# Pump_Driver_Test.net
KiCad netlist of a schematic drawn in Altium Designer
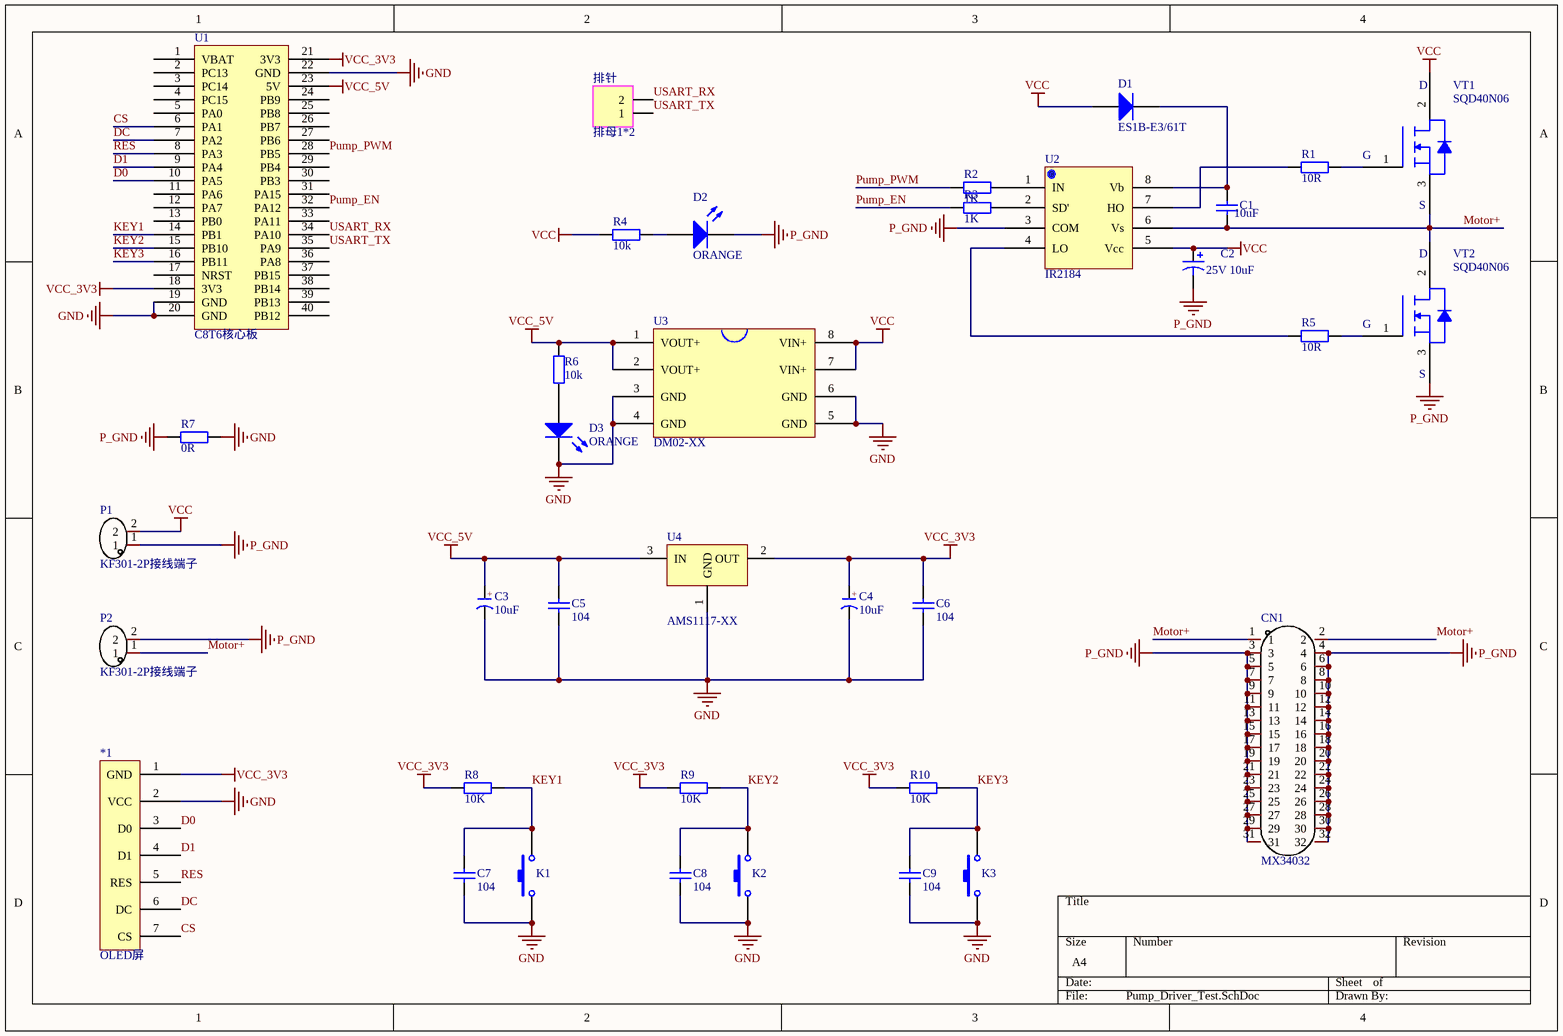
[diagram p0: Pump_Driver_Test.SchDoc]

(export (version "E")
  (design (tool "Eeschema 10.0.6"))
  (components
    (comp (ref "*1") (value "OLED屏") (footprint "HDR2.54-M-LI-7P") (libsource (lib "手柄按钮") (part "OLED屏")))
    (comp (ref "C1")
      (value "10uF")
      (footprint "C 0805")
      (description "无极性电容")
      (libsource (lib "ER100_ESC") (part "Cap"))
    )
    (comp (ref "C2")
      (value "25V 10uF")
      (footprint "CP 3528B")
      (description "极性电容")
      (libsource (lib "ER100_ESC") (part "Cap_Pol"))
    )
    (comp (ref "C3")
      (value "10uF")
      (footprint "CD B(3528)")
      (libsource (lib "USB_Gamepad_board") (part "贴片钽电容"))
    )
    (comp (ref "C4")
      (value "10uF")
      (footprint "CD B(3528)")
      (libsource (lib "USB_Gamepad_board") (part "贴片钽电容"))
    )
    (comp (ref "C5")
      (value "104")
      (footprint "C 0805")
      (description "无极性电容")
      (libsource (lib "HRT_D Schlib") (part "Cap"))
    )
    (comp (ref "C6")
      (value "104")
      (footprint "C 0805")
      (description "无极性电容")
      (libsource (lib "HRT_D Schlib") (part "Cap"))
    )
    (comp (ref "C7")
      (value "104")
      (footprint "C 0805")
      (description "无极性电容")
      (libsource (lib "HRT_D Schlib") (part "Cap"))
    )
    (comp (ref "C8")
      (value "104")
      (footprint "C 0805")
      (description "无极性电容")
      (libsource (lib "HRT_D Schlib") (part "Cap"))
    )
    (comp (ref "C9")
      (value "104")
      (footprint "C 0805")
      (description "无极性电容")
      (libsource (lib "HRT_D Schlib") (part "Cap"))
    )
    (comp (ref "CN1")
      (value "MX34032NF2")
      (footprint "CONN-TH_MX34032NF2")
      (description "间距:2.2mm;插针结构:2x16P;排数:2;每排PIN数:16;行距:3mm;公母:公型插针;安装方式:弯插;")
      (fields (field (name "MANUFACTURER") "JAE(日本航空电子)") (field (name "NAME") "MX34032"))
      (libsource (lib "MX34032") (part "MX34032NF2"))
    )
    (comp (ref "D1")
      (value "ES1B-E3/61T")
      (footprint "DO-214")
      (description "二极管")
      (libsource (lib "ER100_ESC") (part "Diode"))
    )
    (comp (ref "D2")
      (value "ORANGE")
      (footprint "LED_0805")
      (description "发光二极管")
      (libsource (lib "ESC_control") (part "LED"))
    )
    (comp (ref "D3")
      (value "ORANGE")
      (footprint "LED_0805")
      (description "发光二极管")
      (libsource (lib "ESC_control") (part "LED"))
    )
    (comp (ref "K1")
      (value "Key")
      (footprint "KEY 3.6*2.5 SMD")
      (description "按键")
      (libsource (lib "HRT_D Schlib") (part "Key"))
    )
    (comp (ref "K2")
      (value "Key")
      (footprint "KEY 3.6*2.5 SMD")
      (description "按键")
      (libsource (lib "HRT_D Schlib") (part "Key"))
    )
    (comp (ref "K3")
      (value "Key")
      (footprint "KEY 3.6*2.5 SMD")
      (description "按键")
      (libsource (lib "HRT_D Schlib") (part "Key"))
    )
    (comp (ref "P1")
      (value "KF301-2P接线端子")
      (footprint "CONN-TH_XY301V-A-5.0-2P")
      (fields (field (name "NAME") "KF301-2P接线端子"))
      (libsource (lib "KF301_2P") (part "KF301-2P接线端子"))
    )
    (comp (ref "P2")
      (value "KF301-2P接线端子")
      (footprint "CONN-TH_XY301V-A-5.0-2P")
      (fields (field (name "NAME") "KF301-2P接线端子"))
      (libsource (lib "KF301_2P") (part "KF301-2P接线端子"))
    )
    (comp (ref "R1")
      (value "10R")
      (footprint "R 0805")
      (description "电阻")
      (libsource (lib "ER100_ESC") (part "Resistor"))
    )
    (comp (ref "R2")
      (value "1K")
      (footprint "R 0805")
      (description "电阻")
      (libsource (lib "ER100_ESC") (part "Resistor"))
    )
    (comp (ref "R3")
      (value "1K")
      (footprint "R 0805")
      (description "电阻")
      (libsource (lib "ER100_ESC") (part "Resistor"))
    )
    (comp (ref "R4")
      (value "10k")
      (footprint "R 0805")
      (description "电阻")
      (libsource (lib "ESC_control") (part "Resistor"))
    )
    (comp (ref "R5")
      (value "10R")
      (footprint "R 0805")
      (description "电阻")
      (libsource (lib "ER100_ESC") (part "Resistor"))
    )
    (comp (ref "R6")
      (value "10k")
      (footprint "R 0805")
      (description "电阻")
      (libsource (lib "") (part "Resistor_1"))
    )
    (comp (ref "R7")
      (value "0R")
      (footprint "R 0805")
      (description "电阻")
      (libsource (lib "HRT_D Schlib") (part "Resistor"))
    )
    (comp (ref "R8")
      (value "10K")
      (footprint "R 0805")
      (description "电阻")
      (libsource (lib "ESC_control") (part "Resistor"))
    )
    (comp (ref "R9")
      (value "10K")
      (footprint "R 0805")
      (description "电阻")
      (libsource (lib "ESC_control") (part "Resistor"))
    )
    (comp (ref "R10")
      (value "10K")
      (footprint "R 0805")
      (description "电阻")
      (libsource (lib "ESC_control") (part "Resistor"))
    )
    (comp (ref "U1")
      (value "C8T6核心板")
      (footprint "c8t6核心板")
      (libsource (lib "STM32F103C8T6最小系统板") (part "C8T6核心板"))
    )
    (comp (ref "U2")
      (value "IR2184")
      (footprint "SOP8")
      (description "Half-Bridge Gate Driver")
      (libsource (lib "ER100_ESC") (part "IR2184"))
    )
    (comp (ref "U3")
      (value "DM02-XX")
      (footprint "DM02")
      (description "开关型DC-DC变换器")
      (libsource (lib "ESC_control") (part "DM02"))
    )
    (comp (ref "U4")
      (value "AMS1117-XX")
      (footprint "SOT223")
      (description "线性稳压器")
      (libsource (lib "HRT_D Schlib") (part "AMS1117"))
    )
    (comp (ref "VT1")
      (value "SQD40N06")
      (footprint "TO263-3B")
      (libsource (lib "ER100_ESC") (part "PowerMos_N"))
    )
    (comp (ref "VT2")
      (value "SQD40N06")
      (footprint "TO263-3B")
      (libsource (lib "ER100_ESC") (part "PowerMos_N"))
    )
    (comp (ref "排针") (value "排母1*2") (footprint "HDR2.54-M-LI-2P") (libsource (lib "排针排母库") (part "排母1*2")))
  )
  (nets
    (net (code "1") (name "/CS") (class "Default")
      (node (ref "*1") (pin "7") (pinfunction "CS_7") (pintype "passive"))
      (node (ref "U1") (pin "6") (pinfunction "PA1_6") (pintype "passive"))
    )
    (net (code "2") (name "/D0") (class "Default")
      (node (ref "*1") (pin "3") (pinfunction "D0_3") (pintype "passive"))
      (node (ref "U1") (pin "10") (pinfunction "PA5_10") (pintype "passive"))
    )
    (net (code "3") (name "/D1") (class "Default")
      (node (ref "*1") (pin "4") (pinfunction "D1_4") (pintype "passive"))
      (node (ref "U1") (pin "9") (pinfunction "PA4_9") (pintype "passive"))
    )
    (net (code "4") (name "/DC") (class "Default")
      (node (ref "*1") (pin "6") (pinfunction "DC_6") (pintype "passive"))
      (node (ref "U1") (pin "7") (pinfunction "PA2_7") (pintype "passive"))
    )
    (net (code "5") (name "/KEY1") (class "Default")
      (node (ref "C7") (pin "1") (pinfunction "1_1") (pintype "passive"))
      (node (ref "K1") (pin "2") (pinfunction "2_2") (pintype "passive"))
      (node (ref "R8") (pin "1") (pinfunction "1_1") (pintype "passive"))
      (node (ref "U1") (pin "14") (pinfunction "PB1_14") (pintype "passive"))
    )
    (net (code "6") (name "/KEY2") (class "Default")
      (node (ref "C8") (pin "1") (pinfunction "1_1") (pintype "passive"))
      (node (ref "K2") (pin "2") (pinfunction "2_2") (pintype "passive"))
      (node (ref "R9") (pin "1") (pinfunction "1_1") (pintype "passive"))
      (node (ref "U1") (pin "15") (pinfunction "PB10_15") (pintype "passive"))
    )
    (net (code "7") (name "/KEY3") (class "Default")
      (node (ref "C9") (pin "1") (pinfunction "1_1") (pintype "passive"))
      (node (ref "K3") (pin "2") (pinfunction "2_2") (pintype "passive"))
      (node (ref "R10") (pin "1") (pinfunction "1_1") (pintype "passive"))
      (node (ref "U1") (pin "16") (pinfunction "PB11_16") (pintype "passive"))
    )
    (net (code "8") (name "/Motor+") (class "Default")
      (node (ref "C1") (pin "1") (pinfunction "1_1") (pintype "passive"))
      (node (ref "CN1") (pin "1") (pinfunction "1_1") (pintype "passive"))
      (node (ref "CN1") (pin "2") (pinfunction "2_2") (pintype "passive"))
      (node (ref "P2") (pin "1") (pinfunction "1_1") (pintype "passive"))
      (node (ref "U2") (pin "6") (pinfunction "Vs_6") (pintype "passive"))
      (node (ref "VT1") (pin "3") (pinfunction "3_3") (pintype "passive"))
      (node (ref "VT2") (pin "2") (pinfunction "2_2") (pintype "passive"))
    )
    (net (code "9") (name "/Pump_EN") (class "Default")
      (node (ref "R3") (pin "1") (pinfunction "1_1") (pintype "passive"))
      (node (ref "U1") (pin "32") (pinfunction "PA12_32") (pintype "passive"))
    )
    (net (code "10") (name "/Pump_PWM") (class "Default")
      (node (ref "R2") (pin "1") (pinfunction "1_1") (pintype "passive"))
      (node (ref "U1") (pin "28") (pinfunction "PB5_28") (pintype "passive"))
    )
    (net (code "11") (name "/RES") (class "Default")
      (node (ref "*1") (pin "5") (pinfunction "RES_5") (pintype "passive"))
      (node (ref "U1") (pin "8") (pinfunction "PA3_8") (pintype "passive"))
    )
    (net (code "12") (name "/USART_RX") (class "Default")
      (node (ref "U1") (pin "34") (pinfunction "PA10_34") (pintype "passive"))
      (node (ref "排针") (pin "2") (pinfunction "2_2") (pintype "passive"))
    )
    (net (code "13") (name "/USART_TX") (class "Default")
      (node (ref "U1") (pin "35") (pinfunction "PA9_35") (pintype "passive"))
      (node (ref "排针") (pin "1") (pinfunction "1_1") (pintype "passive"))
    )
    (net (code "14") (name "GND") (class "Default")
      (node (ref "*1") (pin "2") (pinfunction "VCC_2") (pintype "passive"))
      (node (ref "C3") (pin "2") (pinfunction "K_2") (pintype "passive"))
      (node (ref "C4") (pin "2") (pinfunction "K_2") (pintype "passive"))
      (node (ref "C5") (pin "2") (pinfunction "2_2") (pintype "passive"))
      (node (ref "C6") (pin "2") (pinfunction "2_2") (pintype "passive"))
      (node (ref "C7") (pin "2") (pinfunction "2_2") (pintype "passive"))
      (node (ref "C8") (pin "2") (pinfunction "2_2") (pintype "passive"))
      (node (ref "C9") (pin "2") (pinfunction "2_2") (pintype "passive"))
      (node (ref "D3") (pin "2") (pinfunction "K_2") (pintype "passive"))
      (node (ref "K1") (pin "1") (pinfunction "1_1") (pintype "passive"))
      (node (ref "K2") (pin "1") (pinfunction "1_1") (pintype "passive"))
      (node (ref "K3") (pin "1") (pinfunction "1_1") (pintype "passive"))
      (node (ref "R7") (pin "2") (pinfunction "2_2") (pintype "passive"))
      (node (ref "U1") (pin "19") (pinfunction "GND_19") (pintype "passive"))
      (node (ref "U1") (pin "20") (pinfunction "GND_20") (pintype "passive"))
      (node (ref "U1") (pin "22") (pinfunction "GND_22") (pintype "passive"))
      (node (ref "U3") (pin "3") (pinfunction "GND_3") (pintype "passive"))
      (node (ref "U3") (pin "4") (pinfunction "GND_4") (pintype "passive"))
      (node (ref "U3") (pin "5") (pinfunction "GND_5") (pintype "passive"))
      (node (ref "U3") (pin "6") (pinfunction "GND_6") (pintype "passive"))
      (node (ref "U4") (pin "1") (pinfunction "GND_1") (pintype "power_in"))
    )
    (net (code "15") (name "Net-(D1-K)") (class "Default")
      (node (ref "C1") (pin "2") (pinfunction "2_2") (pintype "passive"))
      (node (ref "D1") (pin "2") (pinfunction "K_2") (pintype "passive"))
      (node (ref "U2") (pin "8") (pinfunction "Vb_8") (pintype "passive"))
    )
    (net (code "16") (name "Net-(D2-A)") (class "Default")
      (node (ref "D2") (pin "1") (pinfunction "A_1") (pintype "passive"))
      (node (ref "R4") (pin "1") (pinfunction "1_1") (pintype "passive"))
    )
    (net (code "17") (name "Net-(D3-A)") (class "Default")
      (node (ref "D3") (pin "1") (pinfunction "A_1") (pintype "passive"))
      (node (ref "R6") (pin "1") (pinfunction "1_1") (pintype "passive"))
    )
    (net (code "18") (name "Net-(U2-HO)") (class "Default")
      (node (ref "R1") (pin "1") (pinfunction "1_1") (pintype "passive"))
      (node (ref "U2") (pin "7") (pinfunction "HO_7") (pintype "passive"))
    )
    (net (code "19") (name "Net-(U2-IN)") (class "Default")
      (node (ref "R2") (pin "2") (pinfunction "2_2") (pintype "passive"))
      (node (ref "U2") (pin "1") (pinfunction "IN_1") (pintype "passive"))
    )
    (net (code "20") (name "Net-(U2-LO)") (class "Default")
      (node (ref "R5") (pin "1") (pinfunction "1_1") (pintype "passive"))
      (node (ref "U2") (pin "4") (pinfunction "LO_4") (pintype "passive"))
    )
    (net (code "21") (name "Net-(U2-SD')") (class "Default")
      (node (ref "R3") (pin "2") (pinfunction "2_2") (pintype "passive"))
      (node (ref "U2") (pin "2") (pinfunction "SD'_2") (pintype "passive"))
    )
    (net (code "22") (name "Net-(VT1-G)") (class "Default")
      (node (ref "R1") (pin "2") (pinfunction "2_2") (pintype "passive"))
      (node (ref "VT1") (pin "1") (pinfunction "G_1") (pintype "passive"))
    )
    (net (code "23") (name "Net-(VT2-G)") (class "Default")
      (node (ref "R5") (pin "2") (pinfunction "2_2") (pintype "passive"))
      (node (ref "VT2") (pin "1") (pinfunction "G_1") (pintype "passive"))
    )
    (net (code "24") (name "P_GND") (class "Default")
      (node (ref "C2") (pin "2") (pinfunction "2_2") (pintype "passive"))
      (node (ref "CN1") (pin "10") (pinfunction "10_10") (pintype "passive"))
      (node (ref "CN1") (pin "11") (pinfunction "11_11") (pintype "passive"))
      (node (ref "CN1") (pin "12") (pinfunction "12_12") (pintype "passive"))
      (node (ref "CN1") (pin "13") (pinfunction "13_13") (pintype "passive"))
      (node (ref "CN1") (pin "14") (pinfunction "14_14") (pintype "passive"))
      (node (ref "CN1") (pin "15") (pinfunction "15_15") (pintype "passive"))
      (node (ref "CN1") (pin "16") (pinfunction "16_16") (pintype "passive"))
      (node (ref "CN1") (pin "17") (pinfunction "17_17") (pintype "passive"))
      (node (ref "CN1") (pin "18") (pinfunction "18_18") (pintype "passive"))
      (node (ref "CN1") (pin "19") (pinfunction "19_19") (pintype "passive"))
      (node (ref "CN1") (pin "20") (pinfunction "20_20") (pintype "passive"))
      (node (ref "CN1") (pin "21") (pinfunction "21_21") (pintype "passive"))
      (node (ref "CN1") (pin "22") (pinfunction "22_22") (pintype "passive"))
      (node (ref "CN1") (pin "23") (pinfunction "23_23") (pintype "passive"))
      (node (ref "CN1") (pin "24") (pinfunction "24_24") (pintype "passive"))
      (node (ref "CN1") (pin "25") (pinfunction "25_25") (pintype "passive"))
      (node (ref "CN1") (pin "26") (pinfunction "26_26") (pintype "passive"))
      (node (ref "CN1") (pin "27") (pinfunction "27_27") (pintype "passive"))
      (node (ref "CN1") (pin "28") (pinfunction "28_28") (pintype "passive"))
      (node (ref "CN1") (pin "29") (pinfunction "29_29") (pintype "passive"))
      (node (ref "CN1") (pin "3") (pinfunction "3_3") (pintype "passive"))
      (node (ref "CN1") (pin "30") (pinfunction "30_30") (pintype "passive"))
      (node (ref "CN1") (pin "31") (pinfunction "31_31") (pintype "passive"))
      (node (ref "CN1") (pin "32") (pinfunction "32_32") (pintype "passive"))
      (node (ref "CN1") (pin "4") (pinfunction "4_4") (pintype "passive"))
      (node (ref "CN1") (pin "5") (pinfunction "5_5") (pintype "passive"))
      (node (ref "CN1") (pin "6") (pinfunction "6_6") (pintype "passive"))
      (node (ref "CN1") (pin "7") (pinfunction "7_7") (pintype "passive"))
      (node (ref "CN1") (pin "8") (pinfunction "8_8") (pintype "passive"))
      (node (ref "CN1") (pin "9") (pinfunction "9_9") (pintype "passive"))
      (node (ref "D2") (pin "2") (pinfunction "K_2") (pintype "passive"))
      (node (ref "P1") (pin "1") (pinfunction "1_1") (pintype "passive"))
      (node (ref "P2") (pin "2") (pinfunction "2_2") (pintype "passive"))
      (node (ref "R7") (pin "1") (pinfunction "1_1") (pintype "passive"))
      (node (ref "U2") (pin "3") (pinfunction "COM_3") (pintype "passive"))
      (node (ref "VT2") (pin "3") (pinfunction "3_3") (pintype "passive"))
    )
    (net (code "25") (name "VCC") (class "Default")
      (node (ref "C2") (pin "1") (pinfunction "1_1") (pintype "passive"))
      (node (ref "D1") (pin "1") (pinfunction "A_1") (pintype "passive"))
      (node (ref "P1") (pin "2") (pinfunction "2_2") (pintype "passive"))
      (node (ref "R4") (pin "2") (pinfunction "2_2") (pintype "passive"))
      (node (ref "U2") (pin "5") (pinfunction "Vcc_5") (pintype "passive"))
      (node (ref "U3") (pin "7") (pinfunction "VIN+_7") (pintype "passive"))
      (node (ref "U3") (pin "8") (pinfunction "VIN+_8") (pintype "passive"))
      (node (ref "VT1") (pin "2") (pinfunction "2_2") (pintype "passive"))
    )
    (net (code "26") (name "VCC_3V3") (class "Default")
      (node (ref "*1") (pin "1") (pinfunction "GND_1") (pintype "passive"))
      (node (ref "C4") (pin "1") (pinfunction "A_1") (pintype "passive"))
      (node (ref "C6") (pin "1") (pinfunction "1_1") (pintype "passive"))
      (node (ref "R10") (pin "2") (pinfunction "2_2") (pintype "passive"))
      (node (ref "R8") (pin "2") (pinfunction "2_2") (pintype "passive"))
      (node (ref "R9") (pin "2") (pinfunction "2_2") (pintype "passive"))
      (node (ref "U1") (pin "18") (pinfunction "3V3_18") (pintype "passive"))
      (node (ref "U1") (pin "21") (pinfunction "3V3_21") (pintype "passive"))
      (node (ref "U4") (pin "2") (pinfunction "OUT_2") (pintype "power_in"))
    )
    (net (code "27") (name "VCC_5V") (class "Default")
      (node (ref "C3") (pin "1") (pinfunction "A_1") (pintype "passive"))
      (node (ref "C5") (pin "1") (pinfunction "1_1") (pintype "passive"))
      (node (ref "R6") (pin "2") (pinfunction "2_2") (pintype "passive"))
      (node (ref "U1") (pin "23") (pinfunction "5V_23") (pintype "passive"))
      (node (ref "U3") (pin "1") (pinfunction "VOUT+_1") (pintype "passive"))
      (node (ref "U3") (pin "2") (pinfunction "VOUT+_2") (pintype "passive"))
      (node (ref "U4") (pin "3") (pinfunction "IN_3") (pintype "power_in"))
    )
    (net (code "28") (name "unconnected-(U1-NRST-Pad17)") (class "Default")
      (node (ref "U1") (pin "17") (pinfunction "NRST_17") (pintype "passive"))
    )
    (net (code "29") (name "unconnected-(U1-PA0-Pad5)") (class "Default")
      (node (ref "U1") (pin "5") (pinfunction "PA0_5") (pintype "passive"))
    )
    (net (code "30") (name "unconnected-(U1-PA6-Pad11)") (class "Default")
      (node (ref "U1") (pin "11") (pinfunction "PA6_11") (pintype "passive"))
    )
    (net (code "31") (name "unconnected-(U1-PA7-Pad12)") (class "Default")
      (node (ref "U1") (pin "12") (pinfunction "PA7_12") (pintype "passive"))
    )
    (net (code "32") (name "unconnected-(U1-PA8-Pad36)") (class "Default")
      (node (ref "U1") (pin "36") (pinfunction "PA8_36") (pintype "passive"))
    )
    (net (code "33") (name "unconnected-(U1-PA11-Pad33)") (class "Default")
      (node (ref "U1") (pin "33") (pinfunction "PA11_33") (pintype "passive"))
    )
    (net (code "34") (name "unconnected-(U1-PA15-Pad31)") (class "Default")
      (node (ref "U1") (pin "31") (pinfunction "PA15_31") (pintype "passive"))
    )
    (net (code "35") (name "unconnected-(U1-PB0-Pad13)") (class "Default")
      (node (ref "U1") (pin "13") (pinfunction "PB0_13") (pintype "passive"))
    )
    (net (code "36") (name "unconnected-(U1-PB3-Pad30)") (class "Default")
      (node (ref "U1") (pin "30") (pinfunction "PB3_30") (pintype "passive"))
    )
    (net (code "37") (name "unconnected-(U1-PB4-Pad29)") (class "Default")
      (node (ref "U1") (pin "29") (pinfunction "PB4_29") (pintype "passive"))
    )
    (net (code "38") (name "unconnected-(U1-PB6-Pad27)") (class "Default")
      (node (ref "U1") (pin "27") (pinfunction "PB6_27") (pintype "passive"))
    )
    (net (code "39") (name "unconnected-(U1-PB7-Pad26)") (class "Default")
      (node (ref "U1") (pin "26") (pinfunction "PB7_26") (pintype "passive"))
    )
    (net (code "40") (name "unconnected-(U1-PB8-Pad25)") (class "Default")
      (node (ref "U1") (pin "25") (pinfunction "PB8_25") (pintype "passive"))
    )
    (net (code "41") (name "unconnected-(U1-PB9-Pad24)") (class "Default")
      (node (ref "U1") (pin "24") (pinfunction "PB9_24") (pintype "passive"))
    )
    (net (code "42") (name "unconnected-(U1-PB12-Pad40)") (class "Default")
      (node (ref "U1") (pin "40") (pinfunction "PB12_40") (pintype "passive"))
    )
    (net (code "43") (name "unconnected-(U1-PB13-Pad39)") (class "Default")
      (node (ref "U1") (pin "39") (pinfunction "PB13_39") (pintype "passive"))
    )
    (net (code "44") (name "unconnected-(U1-PB14-Pad38)") (class "Default")
      (node (ref "U1") (pin "38") (pinfunction "PB14_38") (pintype "passive"))
    )
    (net (code "45") (name "unconnected-(U1-PB15-Pad37)") (class "Default")
      (node (ref "U1") (pin "37") (pinfunction "PB15_37") (pintype "passive"))
    )
    (net (code "46") (name "unconnected-(U1-PC13-Pad2)") (class "Default")
      (node (ref "U1") (pin "2") (pinfunction "PC13_2") (pintype "passive"))
    )
    (net (code "47") (name "unconnected-(U1-PC14-Pad3)") (class "Default")
      (node (ref "U1") (pin "3") (pinfunction "PC14_3") (pintype "passive"))
    )
    (net (code "48") (name "unconnected-(U1-PC15-Pad4)") (class "Default")
      (node (ref "U1") (pin "4") (pinfunction "PC15_4") (pintype "passive"))
    )
    (net (code "49") (name "unconnected-(U1-VBAT-Pad1)") (class "Default")
      (node (ref "U1") (pin "1") (pinfunction "VBAT_1") (pintype "passive"))
    )
  )
)
